# decoder.net
KiCad netlist of a schematic drawn in EAGLE
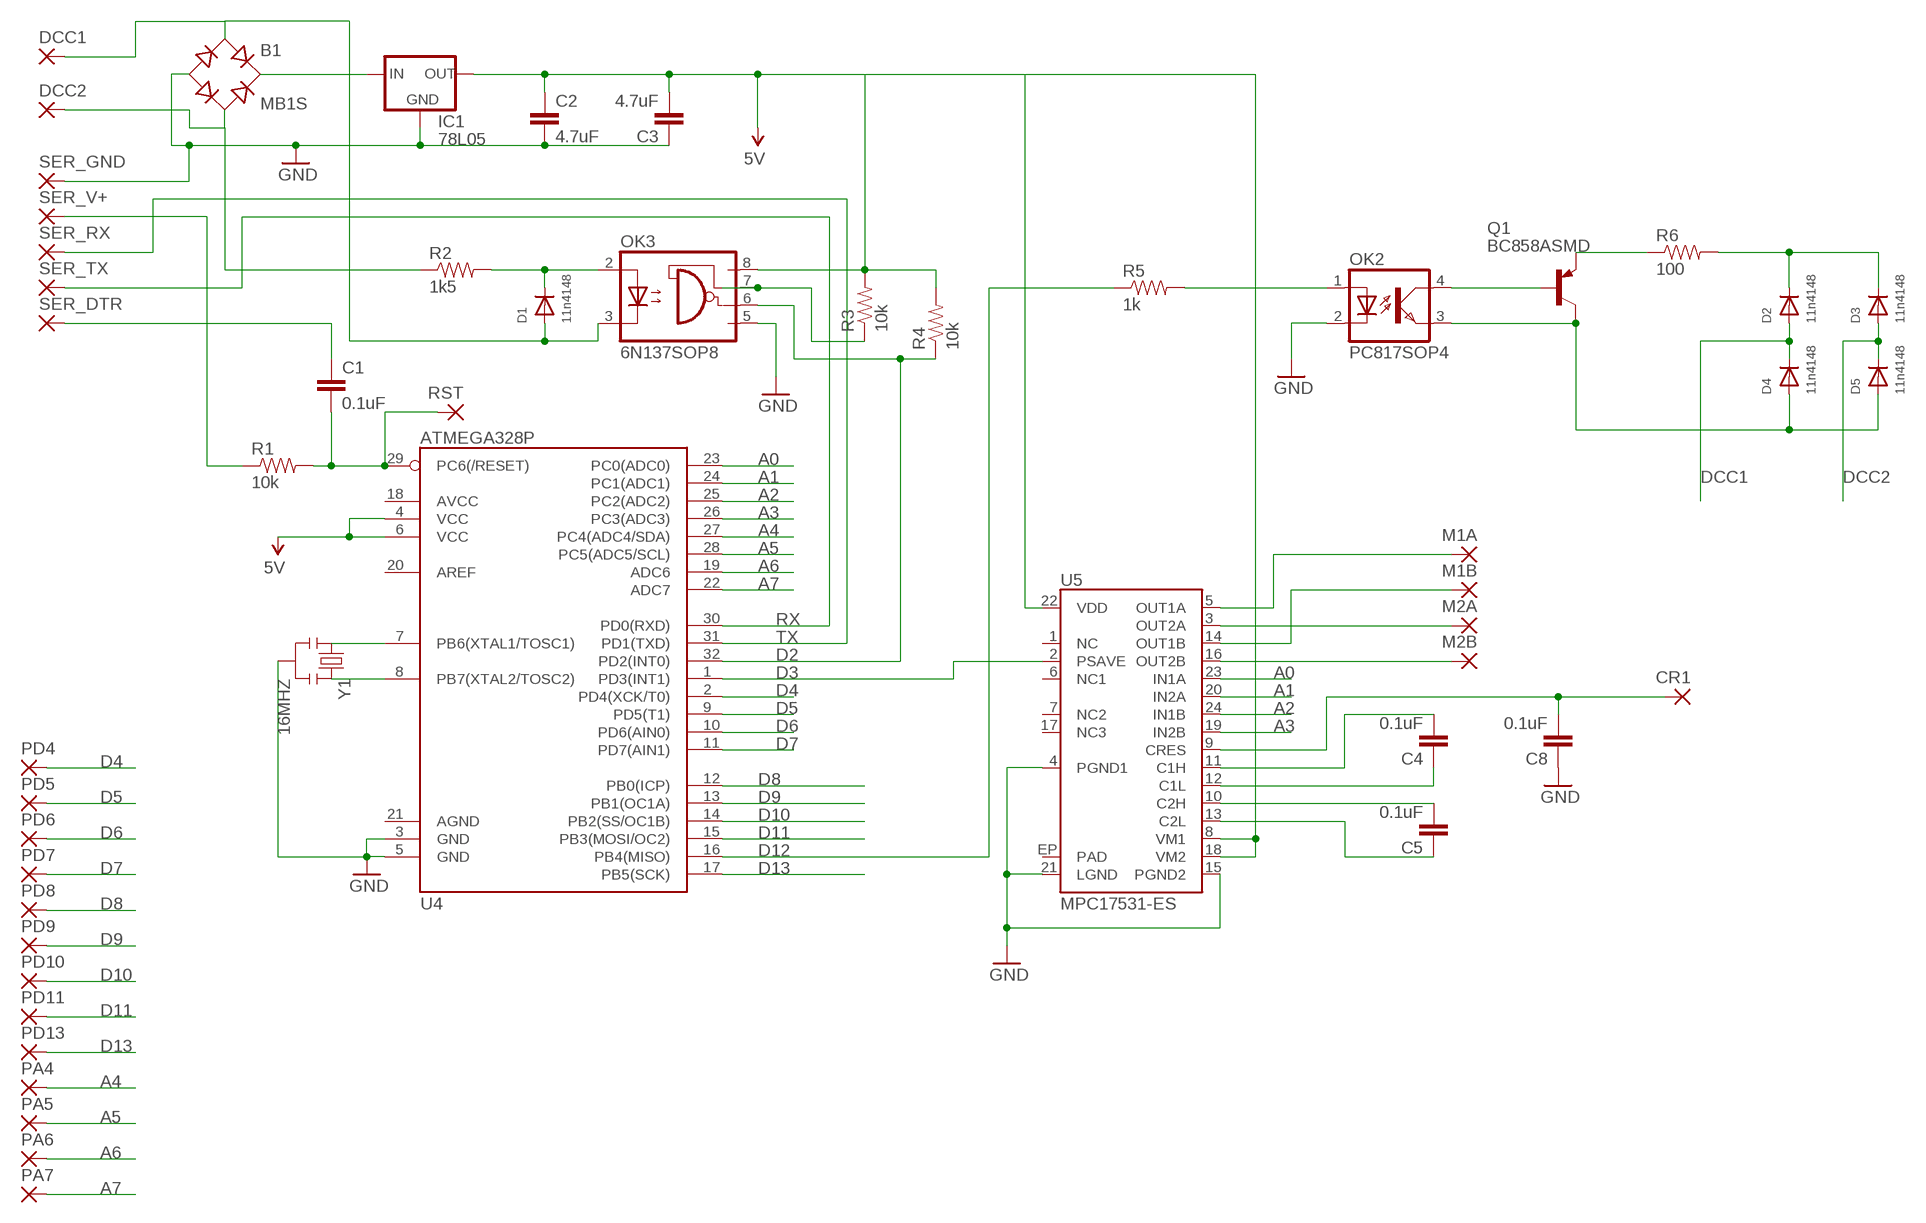
[diagram p0: schematic, sheet 1]

(export (version "E")
  (design (tool "Eeschema 10.0.6"))
  (components
    (comp (ref "B1")
      (value "MB1S")
      (footprint "eagle-import:SOIC-4")
      (libsource (lib "eagle-import") (part "MBS1"))
    )
    (comp (ref "C1")
      (value "0.1uF")
      (footprint "eagle-import:0805")
      (libsource (lib "eagle-import") (part "CAP0805"))
    )
    (comp (ref "C2")
      (value "4.7uF")
      (footprint "eagle-import:0805")
      (libsource (lib "eagle-import") (part "CAP0805"))
    )
    (comp (ref "C3")
      (value "4.7uF")
      (footprint "eagle-import:0805")
      (libsource (lib "eagle-import") (part "CAP0805"))
    )
    (comp (ref "C4")
      (value "0.1uF")
      (footprint "eagle-import:0805")
      (libsource (lib "eagle-import") (part "CAP0805"))
    )
    (comp (ref "C5")
      (value "0.1uF")
      (footprint "eagle-import:0805")
      (libsource (lib "eagle-import") (part "CAP0805"))
    )
    (comp (ref "C8")
      (value "0.1uF")
      (footprint "eagle-import:0805")
      (libsource (lib "eagle-import") (part "CAP0805"))
    )
    (comp (ref "CR1")
      (value "SMD2")
      (footprint "eagle-import:SMD1,27-2,54")
      (libsource (lib "eagle-import") (part "SMD2"))
    )
    (comp (ref "D1")
      (value "11n4148")
      (footprint "eagle-import:SOD-123")
      (libsource (lib "eagle-import") (part "DIODESOD-123"))
    )
    (comp (ref "D2")
      (value "11n4148")
      (footprint "eagle-import:SOD-123")
      (libsource (lib "eagle-import") (part "DIODESOD-123"))
    )
    (comp (ref "D3")
      (value "11n4148")
      (footprint "eagle-import:SOD-123")
      (libsource (lib "eagle-import") (part "DIODESOD-123"))
    )
    (comp (ref "D4")
      (value "11n4148")
      (footprint "eagle-import:SOD-123")
      (libsource (lib "eagle-import") (part "DIODESOD-123"))
    )
    (comp (ref "D5")
      (value "11n4148")
      (footprint "eagle-import:SOD-123")
      (libsource (lib "eagle-import") (part "DIODESOD-123"))
    )
    (comp (ref "DCC1")
      (value "SMD2")
      (footprint "eagle-import:SMD1,27-2,54")
      (libsource (lib "eagle-import") (part "SMD2"))
    )
    (comp (ref "DCC2")
      (value "SMD2")
      (footprint "eagle-import:SMD1,27-2,54")
      (libsource (lib "eagle-import") (part "SMD2"))
    )
    (comp (ref "IC1")
      (value "78L05")
      (footprint "eagle-import:SOT89R")
      (libsource (lib "eagle-import") (part "XC63FPP"))
    )
    (comp (ref "M1A")
      (value "SMD2")
      (footprint "eagle-import:SMD1,27-2,54")
      (libsource (lib "eagle-import") (part "SMD2"))
    )
    (comp (ref "M1B")
      (value "SMD2")
      (footprint "eagle-import:SMD1,27-2,54")
      (libsource (lib "eagle-import") (part "SMD2"))
    )
    (comp (ref "M2A")
      (value "SMD2")
      (footprint "eagle-import:SMD1,27-2,54")
      (libsource (lib "eagle-import") (part "SMD2"))
    )
    (comp (ref "M2B")
      (value "SMD2")
      (footprint "eagle-import:SMD1,27-2,54")
      (libsource (lib "eagle-import") (part "SMD2"))
    )
    (comp (ref "OK2")
      (value "PC817SOP4")
      (footprint "eagle-import:SOP4")
      (libsource (lib "eagle-import") (part "PC817SOP4"))
    )
    (comp (ref "OK3")
      (value "6N137SOP8")
      (footprint "eagle-import:SOIC08")
      (libsource (lib "eagle-import") (part "6N137SOP8"))
    )
    (comp (ref "PA4")
      (value "SMD2")
      (footprint "eagle-import:SMD1,27-2,54")
      (libsource (lib "eagle-import") (part "SMD2"))
    )
    (comp (ref "PA5")
      (value "SMD2")
      (footprint "eagle-import:SMD1,27-2,54")
      (libsource (lib "eagle-import") (part "SMD2"))
    )
    (comp (ref "PA6")
      (value "SMD2")
      (footprint "eagle-import:SMD1,27-2,54")
      (libsource (lib "eagle-import") (part "SMD2"))
    )
    (comp (ref "PA7")
      (value "SMD2")
      (footprint "eagle-import:SMD1,27-2,54")
      (libsource (lib "eagle-import") (part "SMD2"))
    )
    (comp (ref "PD4")
      (value "SMD2")
      (footprint "eagle-import:SMD1,27-2,54")
      (libsource (lib "eagle-import") (part "SMD2"))
    )
    (comp (ref "PD5")
      (value "SMD2")
      (footprint "eagle-import:SMD1,27-2,54")
      (libsource (lib "eagle-import") (part "SMD2"))
    )
    (comp (ref "PD6")
      (value "SMD2")
      (footprint "eagle-import:SMD1,27-2,54")
      (libsource (lib "eagle-import") (part "SMD2"))
    )
    (comp (ref "PD7")
      (value "SMD2")
      (footprint "eagle-import:SMD1,27-2,54")
      (libsource (lib "eagle-import") (part "SMD2"))
    )
    (comp (ref "PD8")
      (value "SMD2")
      (footprint "eagle-import:SMD1,27-2,54")
      (libsource (lib "eagle-import") (part "SMD2"))
    )
    (comp (ref "PD9")
      (value "SMD2")
      (footprint "eagle-import:SMD1,27-2,54")
      (libsource (lib "eagle-import") (part "SMD2"))
    )
    (comp (ref "PD10")
      (value "SMD2")
      (footprint "eagle-import:SMD1,27-2,54")
      (libsource (lib "eagle-import") (part "SMD2"))
    )
    (comp (ref "PD11")
      (value "SMD2")
      (footprint "eagle-import:SMD1,27-2,54")
      (libsource (lib "eagle-import") (part "SMD2"))
    )
    (comp (ref "PD13")
      (value "SMD2")
      (footprint "eagle-import:SMD1,27-2,54")
      (libsource (lib "eagle-import") (part "SMD2"))
    )
    (comp (ref "Q1")
      (value "BC858ASMD")
      (footprint "eagle-import:SOT23-BEC")
      (libsource (lib "eagle-import") (part "BC858SMDA"))
    )
    (comp (ref "R1")
      (value "10k")
      (footprint "eagle-import:0603-RES")
      (libsource (lib "eagle-import") (part "RESISTOR0603-RES"))
    )
    (comp (ref "R2")
      (value "1k5")
      (footprint "eagle-import:0603-RES")
      (libsource (lib "eagle-import") (part "RESISTOR0603-RES"))
    )
    (comp (ref "R3")
      (value "10k")
      (footprint "eagle-import:0603-RES")
      (libsource (lib "eagle-import") (part "RESISTOR0603-RES"))
    )
    (comp (ref "R4")
      (value "10k")
      (footprint "eagle-import:0603-RES")
      (libsource (lib "eagle-import") (part "RESISTOR0603-RES"))
    )
    (comp (ref "R5")
      (value "1k")
      (footprint "eagle-import:0603-RES")
      (libsource (lib "eagle-import") (part "RESISTOR0603-RES"))
    )
    (comp (ref "R6")
      (value "100")
      (footprint "eagle-import:0603-RES")
      (libsource (lib "eagle-import") (part "RESISTOR0603-RES"))
    )
    (comp (ref "RST")
      (value "SMD2")
      (footprint "eagle-import:SMD1,27-2,54")
      (libsource (lib "eagle-import") (part "SMD2"))
    )
    (comp (ref "SER_DTR")
      (value "SMD2")
      (footprint "eagle-import:SMD1,27-2,54")
      (libsource (lib "eagle-import") (part "SMD2"))
    )
    (comp (ref "SER_GND")
      (value "SMD2")
      (footprint "eagle-import:SMD1,27-2,54")
      (libsource (lib "eagle-import") (part "SMD2"))
    )
    (comp (ref "SER_RX")
      (value "SMD2")
      (footprint "eagle-import:SMD1,27-2,54")
      (libsource (lib "eagle-import") (part "SMD2"))
    )
    (comp (ref "SER_TX")
      (value "SMD2")
      (footprint "eagle-import:SMD1,27-2,54")
      (libsource (lib "eagle-import") (part "SMD2"))
    )
    (comp (ref "SER_V+")
      (value "SMD2")
      (footprint "eagle-import:SMD1,27-2,54")
      (libsource (lib "eagle-import") (part "SMD2"))
    )
    (comp (ref "U4")
      (value "ATMEGA328P")
      (footprint "eagle-import:TQFP32-08")
      (libsource (lib "eagle-import") (part "ATMEGA328_SMT"))
    )
    (comp (ref "U5")
      (value "MPC17531-ES")
      (footprint "eagle-import:QFN-24_ALT2")
      (libsource (lib "eagle-import") (part "MPC17531-ES"))
    )
    (comp (ref "Y1")
      (value "16MHZ")
      (footprint "eagle-import:RESONATOR-SMD")
      (libsource (lib "eagle-import") (part "RESONATOR16MHZ"))
    )
  )
  (nets
    (net (code "1") (name "/A0") (class "Default")
      (node (ref "U4") (pin "23") (pinfunction "PC0(ADC0)_23") (pintype "bidirectional"))
      (node (ref "U5") (pin "23") (pinfunction "IN1A_23") (pintype "bidirectional"))
    )
    (net (code "2") (name "/A1") (class "Default")
      (node (ref "U4") (pin "24") (pinfunction "PC1(ADC1)_24") (pintype "bidirectional"))
      (node (ref "U5") (pin "20") (pinfunction "IN2A_20") (pintype "bidirectional"))
    )
    (net (code "3") (name "/A2") (class "Default")
      (node (ref "U4") (pin "25") (pinfunction "PC2(ADC2)_25") (pintype "bidirectional"))
      (node (ref "U5") (pin "24") (pinfunction "IN1B_24") (pintype "bidirectional"))
    )
    (net (code "4") (name "/A3") (class "Default")
      (node (ref "U4") (pin "26") (pinfunction "PC3(ADC3)_26") (pintype "bidirectional"))
      (node (ref "U5") (pin "19") (pinfunction "IN2B_19") (pintype "bidirectional"))
    )
    (net (code "5") (name "/A4") (class "Default")
      (node (ref "PA4") (pin "1") (pinfunction "P_1") (pintype "passive"))
      (node (ref "U4") (pin "27") (pinfunction "PC4(ADC4/SDA)_27") (pintype "bidirectional"))
    )
    (net (code "6") (name "/A5") (class "Default")
      (node (ref "PA5") (pin "1") (pinfunction "P_1") (pintype "passive"))
      (node (ref "U4") (pin "28") (pinfunction "PC5(ADC5/SCL)_28") (pintype "bidirectional"))
    )
    (net (code "7") (name "/A6") (class "Default")
      (node (ref "PA6") (pin "1") (pinfunction "P_1") (pintype "passive"))
      (node (ref "U4") (pin "19") (pinfunction "ADC6_19") (pintype "bidirectional"))
    )
    (net (code "8") (name "/A7") (class "Default")
      (node (ref "PA7") (pin "1") (pinfunction "P_1") (pintype "passive"))
      (node (ref "U4") (pin "22") (pinfunction "ADC7_22") (pintype "bidirectional"))
    )
    (net (code "9") (name "/D2") (class "Default")
      (node (ref "OK3") (pin "6") (pinfunction "VO_6") (pintype "passive"))
      (node (ref "R4") (pin "1") (pinfunction "1_1") (pintype "passive"))
      (node (ref "U4") (pin "32") (pinfunction "PD2(INT0)_32") (pintype "bidirectional"))
    )
    (net (code "10") (name "/D3") (class "Default")
      (node (ref "U4") (pin "1") (pinfunction "PD3(INT1)_1") (pintype "bidirectional"))
      (node (ref "U5") (pin "2") (pinfunction "PSAVE_2") (pintype "bidirectional"))
    )
    (net (code "11") (name "/D4") (class "Default")
      (node (ref "PD4") (pin "1") (pinfunction "P_1") (pintype "passive"))
      (node (ref "U4") (pin "2") (pinfunction "PD4(XCK/T0)_2") (pintype "bidirectional"))
    )
    (net (code "12") (name "/D5") (class "Default")
      (node (ref "PD5") (pin "1") (pinfunction "P_1") (pintype "passive"))
      (node (ref "U4") (pin "9") (pinfunction "PD5(T1)_9") (pintype "bidirectional"))
    )
    (net (code "13") (name "/D6") (class "Default")
      (node (ref "PD6") (pin "1") (pinfunction "P_1") (pintype "passive"))
      (node (ref "U4") (pin "10") (pinfunction "PD6(AIN0)_10") (pintype "bidirectional"))
    )
    (net (code "14") (name "/D7") (class "Default")
      (node (ref "PD7") (pin "1") (pinfunction "P_1") (pintype "passive"))
      (node (ref "U4") (pin "11") (pinfunction "PD7(AIN1)_11") (pintype "bidirectional"))
    )
    (net (code "15") (name "/D8") (class "Default")
      (node (ref "PD8") (pin "1") (pinfunction "P_1") (pintype "passive"))
      (node (ref "U4") (pin "12") (pinfunction "PB0(ICP)_12") (pintype "bidirectional"))
    )
    (net (code "16") (name "/D9") (class "Default")
      (node (ref "PD9") (pin "1") (pinfunction "P_1") (pintype "passive"))
      (node (ref "U4") (pin "13") (pinfunction "PB1(OC1A)_13") (pintype "bidirectional"))
    )
    (net (code "17") (name "/D10") (class "Default")
      (node (ref "PD10") (pin "1") (pinfunction "P_1") (pintype "passive"))
      (node (ref "U4") (pin "14") (pinfunction "PB2(SS/OC1B)_14") (pintype "bidirectional"))
    )
    (net (code "18") (name "/D11") (class "Default")
      (node (ref "PD11") (pin "1") (pinfunction "P_1") (pintype "passive"))
      (node (ref "U4") (pin "15") (pinfunction "PB3(MOSI/OC2)_15") (pintype "bidirectional"))
    )
    (net (code "19") (name "/D12") (class "Default")
      (node (ref "R5") (pin "1") (pinfunction "1_1") (pintype "passive"))
      (node (ref "U4") (pin "16") (pinfunction "PB4(MISO)_16") (pintype "bidirectional"))
    )
    (net (code "20") (name "/D13") (class "Default")
      (node (ref "PD13") (pin "1") (pinfunction "P_1") (pintype "passive"))
      (node (ref "U4") (pin "17") (pinfunction "PB5(SCK)_17") (pintype "bidirectional"))
    )
    (net (code "21") (name "/DCC1") (class "Default")
      (node (ref "B1") (pin "~1") (pinfunction "AC1_~1") (pintype "passive"))
      (node (ref "D1") (pin "A") (pinfunction "A_A") (pintype "passive"))
      (node (ref "D2") (pin "A") (pinfunction "A_A") (pintype "passive"))
      (node (ref "D4") (pin "C") (pinfunction "C_C") (pintype "passive"))
      (node (ref "DCC1") (pin "1") (pinfunction "P_1") (pintype "passive"))
      (node (ref "OK3") (pin "3") (pinfunction "C_3") (pintype "passive"))
    )
    (net (code "22") (name "/DCC2") (class "Default")
      (node (ref "B1") (pin "~2") (pinfunction "AC2_~2") (pintype "passive"))
      (node (ref "D3") (pin "A") (pinfunction "A_A") (pintype "passive"))
      (node (ref "D5") (pin "C") (pinfunction "C_C") (pintype "passive"))
      (node (ref "DCC2") (pin "1") (pinfunction "P_1") (pintype "passive"))
      (node (ref "R2") (pin "1") (pinfunction "1_1") (pintype "passive"))
    )
    (net (code "23") (name "/RX") (class "Default")
      (node (ref "SER_TX") (pin "1") (pinfunction "P_1") (pintype "passive"))
      (node (ref "U4") (pin "30") (pinfunction "PD0(RXD)_30") (pintype "bidirectional"))
    )
    (net (code "24") (name "/TX") (class "Default")
      (node (ref "SER_RX") (pin "1") (pinfunction "P_1") (pintype "passive"))
      (node (ref "U4") (pin "31") (pinfunction "PD1(TXD)_31") (pintype "bidirectional"))
    )
    (net (code "25") (name "5V") (class "Default")
      (node (ref "C2") (pin "1") (pinfunction "1_1") (pintype "passive"))
      (node (ref "C3") (pin "2") (pinfunction "2_2") (pintype "passive"))
      (node (ref "IC1") (pin "3") (pinfunction "OUT_3") (pintype "passive"))
      (node (ref "OK3") (pin "8") (pinfunction "VCC_8") (pintype "passive"))
      (node (ref "R3") (pin "2") (pinfunction "2_2") (pintype "passive"))
      (node (ref "R4") (pin "2") (pinfunction "2_2") (pintype "passive"))
      (node (ref "U4") (pin "4") (pinfunction "VCC_4") (pintype "bidirectional"))
      (node (ref "U4") (pin "6") (pinfunction "VCC_6") (pintype "bidirectional"))
      (node (ref "U5") (pin "18") (pinfunction "VM2_18") (pintype "bidirectional"))
      (node (ref "U5") (pin "8") (pinfunction "VM1_8") (pintype "bidirectional"))
    )
    (net (code "26") (name "GND") (class "Default")
      (node (ref "B1") (pin "-") (pinfunction "-_-") (pintype "passive"))
      (node (ref "C2") (pin "2") (pinfunction "2_2") (pintype "passive"))
      (node (ref "C3") (pin "1") (pinfunction "1_1") (pintype "passive"))
      (node (ref "C8") (pin "1") (pinfunction "1_1") (pintype "passive"))
      (node (ref "IC1") (pin "1") (pinfunction "GND_1") (pintype "input"))
      (node (ref "OK2") (pin "2") (pinfunction "C_2") (pintype "passive"))
      (node (ref "OK3") (pin "5") (pinfunction "GND_5") (pintype "passive"))
      (node (ref "SER_GND") (pin "1") (pinfunction "P_1") (pintype "passive"))
      (node (ref "U4") (pin "3") (pinfunction "GND_3") (pintype "bidirectional"))
      (node (ref "U4") (pin "5") (pinfunction "GND_5") (pintype "bidirectional"))
      (node (ref "U5") (pin "15") (pinfunction "PGND2_15") (pintype "bidirectional"))
      (node (ref "U5") (pin "21") (pinfunction "LGND_21") (pintype "bidirectional"))
      (node (ref "U5") (pin "4") (pinfunction "PGND1_4") (pintype "bidirectional"))
      (node (ref "Y1") (pin "2") (pinfunction "2_2") (pintype "passive"))
    )
    (net (code "27") (name "Net-(CR1-P)") (class "Default")
      (node (ref "C8") (pin "2") (pinfunction "2_2") (pintype "passive"))
      (node (ref "CR1") (pin "1") (pinfunction "P_1") (pintype "passive"))
      (node (ref "U5") (pin "9") (pinfunction "CRES_9") (pintype "bidirectional"))
    )
    (net (code "28") (name "Net-(D2-PadC)") (class "Default")
      (node (ref "D2") (pin "C") (pinfunction "C_C") (pintype "passive"))
      (node (ref "D3") (pin "C") (pinfunction "C_C") (pintype "passive"))
      (node (ref "R6") (pin "2") (pinfunction "2_2") (pintype "passive"))
    )
    (net (code "29") (name "Net-(IC1-IN)") (class "Default")
      (node (ref "B1") (pin "+") (pinfunction "+_+") (pintype "passive"))
      (node (ref "IC1") (pin "2") (pinfunction "IN_2") (pintype "input"))
    )
    (net (code "30") (name "Net-(M1A-P)") (class "Default")
      (node (ref "M1A") (pin "1") (pinfunction "P_1") (pintype "passive"))
      (node (ref "U5") (pin "5") (pinfunction "OUT1A_5") (pintype "bidirectional"))
    )
    (net (code "31") (name "Net-(M1B-P)") (class "Default")
      (node (ref "M1B") (pin "1") (pinfunction "P_1") (pintype "passive"))
      (node (ref "U5") (pin "14") (pinfunction "OUT1B_14") (pintype "bidirectional"))
    )
    (net (code "32") (name "Net-(M2A-P)") (class "Default")
      (node (ref "M2A") (pin "1") (pinfunction "P_1") (pintype "passive"))
      (node (ref "U5") (pin "3") (pinfunction "OUT2A_3") (pintype "bidirectional"))
    )
    (net (code "33") (name "Net-(M2B-P)") (class "Default")
      (node (ref "M2B") (pin "1") (pinfunction "P_1") (pintype "passive"))
      (node (ref "U5") (pin "16") (pinfunction "OUT2B_16") (pintype "bidirectional"))
    )
    (net (code "34") (name "Net-(OK2-A)") (class "Default")
      (node (ref "OK2") (pin "1") (pinfunction "A_1") (pintype "passive"))
      (node (ref "R5") (pin "2") (pinfunction "2_2") (pintype "passive"))
    )
    (net (code "35") (name "Net-(OK2-COL)") (class "Default")
      (node (ref "OK2") (pin "4") (pinfunction "COL_4") (pintype "passive"))
      (node (ref "Q1") (pin "B") (pinfunction "B_B") (pintype "passive"))
    )
    (net (code "36") (name "Net-(OK2-EMIT)") (class "Default")
      (node (ref "D4") (pin "A") (pinfunction "A_A") (pintype "passive"))
      (node (ref "D5") (pin "A") (pinfunction "A_A") (pintype "passive"))
      (node (ref "OK2") (pin "3") (pinfunction "EMIT_3") (pintype "passive"))
      (node (ref "Q1") (pin "C") (pinfunction "C_C") (pintype "passive"))
    )
    (net (code "37") (name "Net-(OK3-A)") (class "Default")
      (node (ref "D1") (pin "C") (pinfunction "C_C") (pintype "passive"))
      (node (ref "OK3") (pin "2") (pinfunction "A_2") (pintype "passive"))
      (node (ref "R2") (pin "2") (pinfunction "2_2") (pintype "passive"))
    )
    (net (code "38") (name "Net-(OK3-VE)") (class "Default")
      (node (ref "OK3") (pin "7") (pinfunction "VE_7") (pintype "passive"))
      (node (ref "R3") (pin "1") (pinfunction "1_1") (pintype "passive"))
    )
    (net (code "39") (name "Net-(Q1-PadE)") (class "Default")
      (node (ref "Q1") (pin "E") (pinfunction "E_E") (pintype "passive"))
      (node (ref "R6") (pin "1") (pinfunction "1_1") (pintype "passive"))
    )
    (net (code "40") (name "Net-(RST-P)") (class "Default")
      (node (ref "C1") (pin "2") (pinfunction "2_2") (pintype "passive"))
      (node (ref "R1") (pin "2") (pinfunction "2_2") (pintype "passive"))
      (node (ref "RST") (pin "1") (pinfunction "P_1") (pintype "passive"))
      (node (ref "U4") (pin "29") (pinfunction "PC6(/RESET)_29") (pintype "bidirectional"))
    )
    (net (code "41") (name "Net-(SER_DTR-P)") (class "Default")
      (node (ref "C1") (pin "1") (pinfunction "1_1") (pintype "passive"))
      (node (ref "SER_DTR") (pin "1") (pinfunction "P_1") (pintype "passive"))
    )
    (net (code "42") (name "Net-(SER_V+-P)") (class "Default")
      (node (ref "R1") (pin "1") (pinfunction "1_1") (pintype "passive"))
      (node (ref "SER_V+") (pin "1") (pinfunction "P_1") (pintype "passive"))
    )
    (net (code "43") (name "Net-(U4-PB6(XTAL1{slash}TOSC1))") (class "Default")
      (node (ref "U4") (pin "7") (pinfunction "PB6(XTAL1/TOSC1)_7") (pintype "bidirectional"))
      (node (ref "Y1") (pin "1") (pinfunction "1_1") (pintype "passive"))
    )
    (net (code "44") (name "Net-(U4-PB7(XTAL2{slash}TOSC2))") (class "Default")
      (node (ref "U4") (pin "8") (pinfunction "PB7(XTAL2/TOSC2)_8") (pintype "bidirectional"))
      (node (ref "Y1") (pin "3") (pinfunction "3_3") (pintype "passive"))
    )
    (net (code "45") (name "Net-(U5-C1H)") (class "Default")
      (node (ref "C4") (pin "2") (pinfunction "2_2") (pintype "passive"))
      (node (ref "U5") (pin "11") (pinfunction "C1H_11") (pintype "bidirectional"))
    )
    (net (code "46") (name "Net-(U5-C1L)") (class "Default")
      (node (ref "C4") (pin "1") (pinfunction "1_1") (pintype "passive"))
      (node (ref "U5") (pin "12") (pinfunction "C1L_12") (pintype "bidirectional"))
    )
    (net (code "47") (name "Net-(U5-C2H)") (class "Default")
      (node (ref "C5") (pin "2") (pinfunction "2_2") (pintype "passive"))
      (node (ref "U5") (pin "10") (pinfunction "C2H_10") (pintype "bidirectional"))
    )
    (net (code "48") (name "Net-(U5-C2L)") (class "Default")
      (node (ref "C5") (pin "1") (pinfunction "1_1") (pintype "passive"))
      (node (ref "U5") (pin "13") (pinfunction "C2L_13") (pintype "bidirectional"))
    )
    (net (code "49") (name "unconnected-(U4-AGND-Pad21)") (class "Default")
      (node (ref "U4") (pin "21") (pinfunction "AGND_21") (pintype "bidirectional"))
    )
    (net (code "50") (name "unconnected-(U4-AREF-Pad20)") (class "Default")
      (node (ref "U4") (pin "20") (pinfunction "AREF_20") (pintype "bidirectional"))
    )
    (net (code "51") (name "unconnected-(U4-AVCC-Pad18)") (class "Default")
      (node (ref "U4") (pin "18") (pinfunction "AVCC_18") (pintype "bidirectional"))
    )
    (net (code "52") (name "unconnected-(U5-NC-Pad1)") (class "Default")
      (node (ref "U5") (pin "1") (pinfunction "NC_1") (pintype "bidirectional"))
    )
    (net (code "53") (name "unconnected-(U5-NC1-Pad6)") (class "Default")
      (node (ref "U5") (pin "6") (pinfunction "NC1_6") (pintype "bidirectional"))
    )
    (net (code "54") (name "unconnected-(U5-NC2-Pad7)") (class "Default")
      (node (ref "U5") (pin "7") (pinfunction "NC2_7") (pintype "bidirectional"))
    )
    (net (code "55") (name "unconnected-(U5-NC3-Pad17)") (class "Default")
      (node (ref "U5") (pin "17") (pinfunction "NC3_17") (pintype "bidirectional"))
    )
    (net (code "56") (name "unconnected-(U5-PAD-PadEP)") (class "Default")
      (node (ref "U5") (pin "EP") (pinfunction "PAD_EP") (pintype "bidirectional"))
    )
    (net (code "57") (name "unconnected-(U5-VDD-Pad22)") (class "Default")
      (node (ref "U5") (pin "22") (pinfunction "VDD_22") (pintype "bidirectional"))
    )
  )
)
